# Sch1.net
KiCad netlist of a schematic drawn in EAGLE
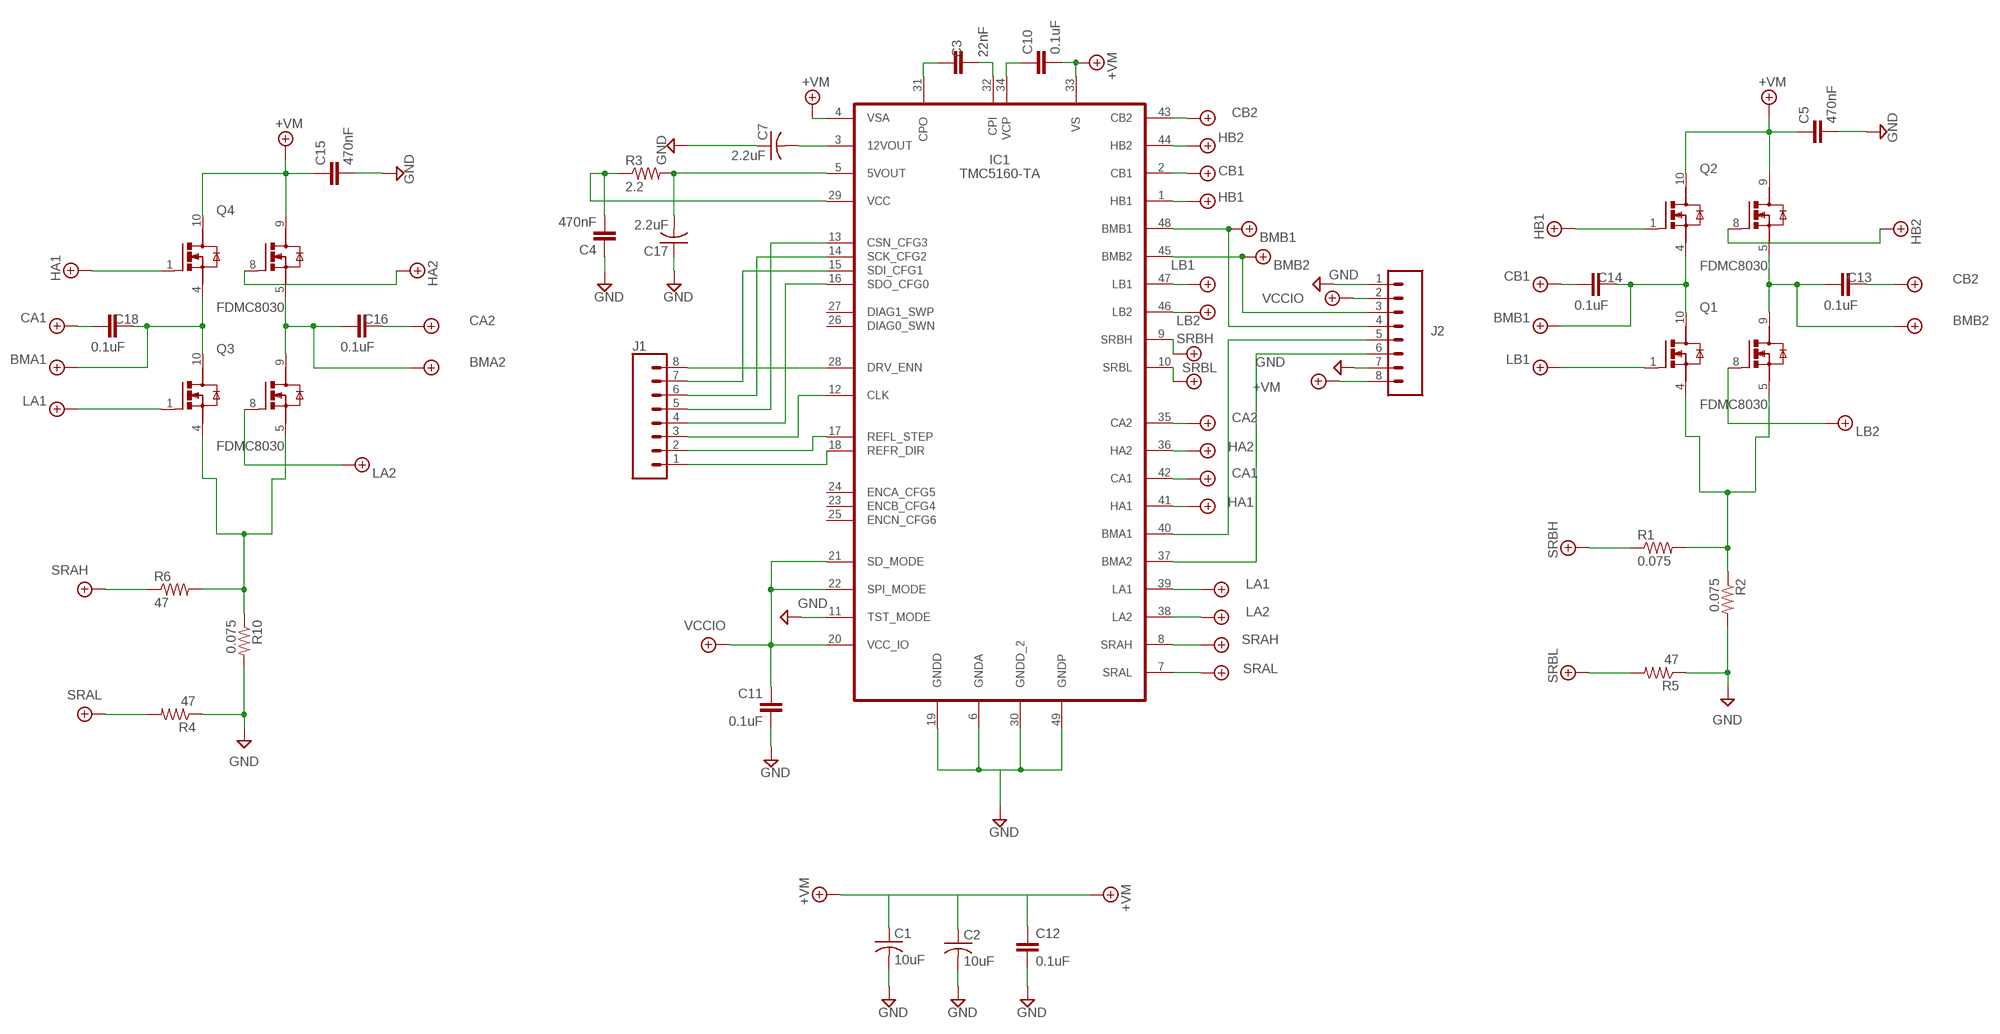
[diagram p0: schematic, sheet 1]

(export (version "E")
  (design (tool "Eeschema 10.0.6"))
  (components
    (comp (ref "C1")
      (value "10uF")
      (footprint "eagle-import:C0805")
      (libsource (lib "eagle-import") (part "C-USC0805"))
    )
    (comp (ref "C2")
      (value "10uF")
      (footprint "eagle-import:C0805")
      (libsource (lib "eagle-import") (part "C-USC0805"))
    )
    (comp (ref "C3")
      (value "22nF")
      (footprint "eagle-import:0603")
      (libsource (lib "eagle-import") (part "22NF/22,000PF-0603-50V-10%"))
    )
    (comp (ref "C4")
      (value "470nF")
      (footprint "eagle-import:0402")
      (libsource (lib "eagle-import") (part "470NF-0402-16V-10%"))
    )
    (comp (ref "C5")
      (value "470nF")
      (footprint "eagle-import:0402")
      (libsource (lib "eagle-import") (part "470NF-0402-16V-10%"))
    )
    (comp (ref "C7")
      (value "2.2uF")
      (footprint "eagle-import:C0402")
      (libsource (lib "eagle-import") (part "C-USC0402"))
    )
    (comp (ref "C10")
      (value "0.1uF")
      (footprint "eagle-import:0402")
      (libsource (lib "eagle-import") (part "0.1UF-0402-16V-10%"))
    )
    (comp (ref "C11")
      (value "0.1uF")
      (footprint "eagle-import:0402")
      (libsource (lib "eagle-import") (part "0.1UF-0402-16V-10%"))
    )
    (comp (ref "C12")
      (value "0.1uF")
      (footprint "eagle-import:0402")
      (libsource (lib "eagle-import") (part "0.1UF-0402-16V-10%"))
    )
    (comp (ref "C13")
      (value "0.1uF")
      (footprint "eagle-import:0402")
      (libsource (lib "eagle-import") (part "0.1UF-0402-16V-10%"))
    )
    (comp (ref "C14")
      (value "0.1uF")
      (footprint "eagle-import:0402")
      (libsource (lib "eagle-import") (part "0.1UF-0402-16V-10%"))
    )
    (comp (ref "C15")
      (value "470nF")
      (footprint "eagle-import:0402")
      (libsource (lib "eagle-import") (part "470NF-0402-16V-10%"))
    )
    (comp (ref "C16")
      (value "0.1uF")
      (footprint "eagle-import:0402")
      (libsource (lib "eagle-import") (part "0.1UF-0402-16V-10%"))
    )
    (comp (ref "C17")
      (value "2.2uF")
      (footprint "eagle-import:C0402")
      (libsource (lib "eagle-import") (part "C-USC0402"))
    )
    (comp (ref "C18")
      (value "0.1uF")
      (footprint "eagle-import:0402")
      (libsource (lib "eagle-import") (part "0.1UF-0402-16V-10%"))
    )
    (comp (ref "IC1")
      (value "TMC5160-TA")
      (footprint "eagle-import:TQFP48-EP")
      (fields (field (name "MF") "Trinamic Motion"))
      (libsource (lib "eagle-import") (part "TMC5160-TA"))
    )
    (comp (ref "J1")
      (value "CONN_08\"")
      (footprint "eagle-import:1X08")
      (libsource (lib "eagle-import") (part "CONN_08{dblquote}"))
    )
    (comp (ref "J2")
      (value "CONN_08\"")
      (footprint "eagle-import:1X08")
      (libsource (lib "eagle-import") (part "CONN_08{dblquote}"))
    )
    (comp (ref "Q1")
      (value "FDMC8030")
      (footprint "eagle-import:TRANS_FDMC8030")
      (fields (field (name "MF") "ON Semiconductor"))
      (libsource (lib "eagle-import") (part "FDMC8030"))
    )
    (comp (ref "Q2")
      (value "FDMC8030")
      (footprint "eagle-import:TRANS_FDMC8030")
      (fields (field (name "MF") "ON Semiconductor"))
      (libsource (lib "eagle-import") (part "FDMC8030"))
    )
    (comp (ref "Q3")
      (value "FDMC8030")
      (footprint "eagle-import:TRANS_FDMC8030")
      (fields (field (name "MF") "ON Semiconductor"))
      (libsource (lib "eagle-import") (part "FDMC8030"))
    )
    (comp (ref "Q4")
      (value "FDMC8030")
      (footprint "eagle-import:TRANS_FDMC8030")
      (fields (field (name "MF") "ON Semiconductor"))
      (libsource (lib "eagle-import") (part "FDMC8030"))
    )
    (comp (ref "R1")
      (value "0.075")
      (footprint "eagle-import:R1206")
      (libsource (lib "eagle-import") (part "R-US_R1206"))
    )
    (comp (ref "R2")
      (value "0.075")
      (footprint "eagle-import:R1206")
      (libsource (lib "eagle-import") (part "R-US_R1206"))
    )
    (comp (ref "R3")
      (value "2.2")
      (footprint "eagle-import:R0402")
      (libsource (lib "eagle-import") (part "R-US_R0402"))
    )
    (comp (ref "R4")
      (value "47")
      (footprint "eagle-import:R0402")
      (libsource (lib "eagle-import") (part "R-US_R0402"))
    )
    (comp (ref "R5")
      (value "47")
      (footprint "eagle-import:R0402")
      (libsource (lib "eagle-import") (part "R-US_R0402"))
    )
    (comp (ref "R6")
      (value "47")
      (footprint "eagle-import:R0402")
      (libsource (lib "eagle-import") (part "R-US_R0402"))
    )
    (comp (ref "R10")
      (value "0.075")
      (footprint "eagle-import:R1206")
      (libsource (lib "eagle-import") (part "R-US_R1206"))
    )
  )
  (nets
    (net (code "1") (name "+VM") (class "Default")
      (node (ref "C1") (pin "1") (pinfunction "1_1") (pintype "passive"))
      (node (ref "C10") (pin "2") (pinfunction "2_2") (pintype "passive"))
      (node (ref "C12") (pin "1") (pinfunction "1_1") (pintype "passive"))
      (node (ref "C13") (pin "1") (pinfunction "1_1") (pintype "passive"))
      (node (ref "C13") (pin "2") (pinfunction "2_2") (pintype "passive"))
      (node (ref "C14") (pin "1") (pinfunction "1_1") (pintype "passive"))
      (node (ref "C14") (pin "2") (pinfunction "2_2") (pintype "passive"))
      (node (ref "C15") (pin "1") (pinfunction "1_1") (pintype "passive"))
      (node (ref "C16") (pin "1") (pinfunction "1_1") (pintype "passive"))
      (node (ref "C16") (pin "2") (pinfunction "2_2") (pintype "passive"))
      (node (ref "C18") (pin "1") (pinfunction "1_1") (pintype "passive"))
      (node (ref "C18") (pin "2") (pinfunction "2_2") (pintype "passive"))
      (node (ref "C2") (pin "1") (pinfunction "1_1") (pintype "passive"))
      (node (ref "C5") (pin "1") (pinfunction "1_1") (pintype "passive"))
      (node (ref "IC1") (pin "1") (pinfunction "HB1_1") (pintype "output"))
      (node (ref "IC1") (pin "10") (pinfunction "SRBL_10") (pintype "input"))
      (node (ref "IC1") (pin "2") (pinfunction "CB1_2") (pintype "input"))
      (node (ref "IC1") (pin "33") (pinfunction "VS_33") (pintype "power_in"))
      (node (ref "IC1") (pin "35") (pinfunction "CA2_35") (pintype "input"))
      (node (ref "IC1") (pin "36") (pinfunction "HA2_36") (pintype "output"))
      (node (ref "IC1") (pin "38") (pinfunction "LA2_38") (pintype "output"))
      (node (ref "IC1") (pin "39") (pinfunction "LA1_39") (pintype "output"))
      (node (ref "IC1") (pin "4") (pinfunction "VSA_4") (pintype "power_in"))
      (node (ref "IC1") (pin "41") (pinfunction "HA1_41") (pintype "output"))
      (node (ref "IC1") (pin "42") (pinfunction "CA1_42") (pintype "input"))
      (node (ref "IC1") (pin "43") (pinfunction "CB2_43") (pintype "input"))
      (node (ref "IC1") (pin "44") (pinfunction "HB2_44") (pintype "output"))
      (node (ref "IC1") (pin "45") (pinfunction "BMB2_45") (pintype "input"))
      (node (ref "IC1") (pin "46") (pinfunction "LB2_46") (pintype "output"))
      (node (ref "IC1") (pin "47") (pinfunction "LB1_47") (pintype "output"))
      (node (ref "IC1") (pin "48") (pinfunction "BMB1_48") (pintype "input"))
      (node (ref "IC1") (pin "7") (pinfunction "SRAL_7") (pintype "input"))
      (node (ref "IC1") (pin "8") (pinfunction "SRAH_8") (pintype "input"))
      (node (ref "IC1") (pin "9") (pinfunction "SRBH_9") (pintype "input"))
      (node (ref "J2") (pin "3") (pinfunction "3_3") (pintype "passive"))
      (node (ref "J2") (pin "4") (pinfunction "4_4") (pintype "passive"))
      (node (ref "J2") (pin "8") (pinfunction "8_8") (pintype "passive"))
      (node (ref "Q1") (pin "1") (pinfunction "G1_1") (pintype "passive"))
      (node (ref "Q1") (pin "10") (pinfunction "D1_10") (pintype "passive"))
      (node (ref "Q1") (pin "8") (pinfunction "G2_8") (pintype "passive"))
      (node (ref "Q1") (pin "9") (pinfunction "D2_9") (pintype "passive"))
      (node (ref "Q2") (pin "1") (pinfunction "G1_1") (pintype "passive"))
      (node (ref "Q2") (pin "10") (pinfunction "D1_10") (pintype "passive"))
      (node (ref "Q2") (pin "4") (pinfunction "S1_4") (pintype "passive"))
      (node (ref "Q2") (pin "5") (pinfunction "S2_5") (pintype "passive"))
      (node (ref "Q2") (pin "8") (pinfunction "G2_8") (pintype "passive"))
      (node (ref "Q2") (pin "9") (pinfunction "D2_9") (pintype "passive"))
      (node (ref "Q3") (pin "1") (pinfunction "G1_1") (pintype "passive"))
      (node (ref "Q3") (pin "10") (pinfunction "D1_10") (pintype "passive"))
      (node (ref "Q3") (pin "8") (pinfunction "G2_8") (pintype "passive"))
      (node (ref "Q3") (pin "9") (pinfunction "D2_9") (pintype "passive"))
      (node (ref "Q4") (pin "1") (pinfunction "G1_1") (pintype "passive"))
      (node (ref "Q4") (pin "10") (pinfunction "D1_10") (pintype "passive"))
      (node (ref "Q4") (pin "4") (pinfunction "S1_4") (pintype "passive"))
      (node (ref "Q4") (pin "5") (pinfunction "S2_5") (pintype "passive"))
      (node (ref "Q4") (pin "8") (pinfunction "G2_8") (pintype "passive"))
      (node (ref "Q4") (pin "9") (pinfunction "D2_9") (pintype "passive"))
      (node (ref "R1") (pin "1") (pinfunction "1_1") (pintype "passive"))
      (node (ref "R4") (pin "2") (pinfunction "2_2") (pintype "passive"))
      (node (ref "R5") (pin "2") (pinfunction "2_2") (pintype "passive"))
      (node (ref "R6") (pin "1") (pinfunction "1_1") (pintype "passive"))
    )
    (net (code "2") (name "GND") (class "Default")
      (node (ref "C1") (pin "2") (pinfunction "2_2") (pintype "passive"))
      (node (ref "C11") (pin "2") (pinfunction "2_2") (pintype "passive"))
      (node (ref "C12") (pin "2") (pinfunction "2_2") (pintype "passive"))
      (node (ref "C15") (pin "2") (pinfunction "2_2") (pintype "passive"))
      (node (ref "C17") (pin "1") (pinfunction "1_1") (pintype "passive"))
      (node (ref "C2") (pin "2") (pinfunction "2_2") (pintype "passive"))
      (node (ref "C4") (pin "1") (pinfunction "1_1") (pintype "passive"))
      (node (ref "C5") (pin "2") (pinfunction "2_2") (pintype "passive"))
      (node (ref "C7") (pin "1") (pinfunction "1_1") (pintype "passive"))
      (node (ref "IC1") (pin "11") (pinfunction "TST_MODE_11") (pintype "input"))
      (node (ref "IC1") (pin "19") (pinfunction "GNDD_19") (pintype "power_in"))
      (node (ref "IC1") (pin "30") (pinfunction "GNDD_2_30") (pintype "power_in"))
      (node (ref "IC1") (pin "49") (pinfunction "GNDP_49") (pintype "power_in"))
      (node (ref "IC1") (pin "6") (pinfunction "GNDA_6") (pintype "power_in"))
      (node (ref "J2") (pin "1") (pinfunction "1_1") (pintype "passive"))
      (node (ref "J2") (pin "7") (pinfunction "7_7") (pintype "passive"))
      (node (ref "R10") (pin "2") (pinfunction "2_2") (pintype "passive"))
      (node (ref "R2") (pin "2") (pinfunction "2_2") (pintype "passive"))
      (node (ref "R4") (pin "1") (pinfunction "1_1") (pintype "passive"))
      (node (ref "R5") (pin "1") (pinfunction "1_1") (pintype "passive"))
    )
    (net (code "3") (name "Net-(IC1-5VOUT)") (class "Default")
      (node (ref "C17") (pin "2") (pinfunction "2_2") (pintype "passive"))
      (node (ref "IC1") (pin "5") (pinfunction "5VOUT_5") (pintype "bidirectional"))
      (node (ref "R3") (pin "2") (pinfunction "2_2") (pintype "passive"))
    )
    (net (code "4") (name "Net-(IC1-12VOUT)") (class "Default")
      (node (ref "C7") (pin "2") (pinfunction "2_2") (pintype "passive"))
      (node (ref "IC1") (pin "3") (pinfunction "12VOUT_3") (pintype "bidirectional"))
    )
    (net (code "5") (name "Net-(IC1-BMA1)") (class "Default")
      (node (ref "IC1") (pin "40") (pinfunction "BMA1_40") (pintype "input"))
      (node (ref "J2") (pin "5") (pinfunction "5_5") (pintype "passive"))
    )
    (net (code "6") (name "Net-(IC1-BMA2)") (class "Default")
      (node (ref "IC1") (pin "37") (pinfunction "BMA2_37") (pintype "input"))
      (node (ref "J2") (pin "6") (pinfunction "6_6") (pintype "passive"))
    )
    (net (code "7") (name "Net-(IC1-CLK)") (class "Default")
      (node (ref "IC1") (pin "12") (pinfunction "CLK_12") (pintype "input"))
      (node (ref "J1") (pin "3") (pinfunction "3_3") (pintype "passive"))
    )
    (net (code "8") (name "Net-(IC1-CPI)") (class "Default")
      (node (ref "C3") (pin "2") (pinfunction "2_2") (pintype "passive"))
      (node (ref "IC1") (pin "32") (pinfunction "CPI_32") (pintype "input"))
    )
    (net (code "9") (name "Net-(IC1-CPO)") (class "Default")
      (node (ref "C3") (pin "1") (pinfunction "1_1") (pintype "passive"))
      (node (ref "IC1") (pin "31") (pinfunction "CPO_31") (pintype "input"))
    )
    (net (code "10") (name "Net-(IC1-CSN_CFG3)") (class "Default")
      (node (ref "IC1") (pin "13") (pinfunction "CSN_CFG3_13") (pintype "input"))
      (node (ref "J1") (pin "5") (pinfunction "5_5") (pintype "passive"))
    )
    (net (code "11") (name "Net-(IC1-DRV_ENN)") (class "Default")
      (node (ref "IC1") (pin "28") (pinfunction "DRV_ENN_28") (pintype "input"))
      (node (ref "J1") (pin "8") (pinfunction "8_8") (pintype "passive"))
    )
    (net (code "12") (name "Net-(IC1-REFL_STEP)") (class "Default")
      (node (ref "IC1") (pin "17") (pinfunction "REFL_STEP_17") (pintype "input"))
      (node (ref "J1") (pin "2") (pinfunction "2_2") (pintype "passive"))
    )
    (net (code "13") (name "Net-(IC1-REFR_DIR)") (class "Default")
      (node (ref "IC1") (pin "18") (pinfunction "REFR_DIR_18") (pintype "input"))
      (node (ref "J1") (pin "1") (pinfunction "1_1") (pintype "passive"))
    )
    (net (code "14") (name "Net-(IC1-SCK_CFG2)") (class "Default")
      (node (ref "IC1") (pin "14") (pinfunction "SCK_CFG2_14") (pintype "input"))
      (node (ref "J1") (pin "6") (pinfunction "6_6") (pintype "passive"))
    )
    (net (code "15") (name "Net-(IC1-SDI_CFG1)") (class "Default")
      (node (ref "IC1") (pin "15") (pinfunction "SDI_CFG1_15") (pintype "input"))
      (node (ref "J1") (pin "7") (pinfunction "7_7") (pintype "passive"))
    )
    (net (code "16") (name "Net-(IC1-SDO_CFG0)") (class "Default")
      (node (ref "IC1") (pin "16") (pinfunction "SDO_CFG0_16") (pintype "output"))
      (node (ref "J1") (pin "4") (pinfunction "4_4") (pintype "passive"))
    )
    (net (code "17") (name "Net-(IC1-VCC)") (class "Default")
      (node (ref "C4") (pin "2") (pinfunction "2_2") (pintype "passive"))
      (node (ref "IC1") (pin "29") (pinfunction "VCC_29") (pintype "power_in"))
      (node (ref "R3") (pin "1") (pinfunction "1_1") (pintype "passive"))
    )
    (net (code "18") (name "Net-(IC1-VCP)") (class "Default")
      (node (ref "C10") (pin "1") (pinfunction "1_1") (pintype "passive"))
      (node (ref "IC1") (pin "34") (pinfunction "VCP_34") (pintype "input"))
    )
    (net (code "19") (name "Net-(Q1-S1)") (class "Default")
      (node (ref "Q1") (pin "4") (pinfunction "S1_4") (pintype "passive"))
      (node (ref "Q1") (pin "5") (pinfunction "S2_5") (pintype "passive"))
      (node (ref "R1") (pin "2") (pinfunction "2_2") (pintype "passive"))
      (node (ref "R2") (pin "1") (pinfunction "1_1") (pintype "passive"))
    )
    (net (code "20") (name "Net-(Q3-S1)") (class "Default")
      (node (ref "Q3") (pin "4") (pinfunction "S1_4") (pintype "passive"))
      (node (ref "Q3") (pin "5") (pinfunction "S2_5") (pintype "passive"))
      (node (ref "R10") (pin "1") (pinfunction "1_1") (pintype "passive"))
      (node (ref "R6") (pin "2") (pinfunction "2_2") (pintype "passive"))
    )
    (net (code "21") (name "VCCIO") (class "Default")
      (node (ref "C11") (pin "1") (pinfunction "1_1") (pintype "passive"))
      (node (ref "IC1") (pin "20") (pinfunction "VCC_IO_20") (pintype "power_in"))
      (node (ref "IC1") (pin "21") (pinfunction "SD_MODE_21") (pintype "input"))
      (node (ref "IC1") (pin "22") (pinfunction "SPI_MODE_22") (pintype "input"))
      (node (ref "J2") (pin "2") (pinfunction "2_2") (pintype "passive"))
    )
    (net (code "22") (name "unconnected-(IC1-DIAG0_SWN-Pad26)") (class "Default")
      (node (ref "IC1") (pin "26") (pinfunction "DIAG0_SWN_26") (pintype "bidirectional"))
    )
    (net (code "23") (name "unconnected-(IC1-DIAG1_SWP-Pad27)") (class "Default")
      (node (ref "IC1") (pin "27") (pinfunction "DIAG1_SWP_27") (pintype "bidirectional"))
    )
    (net (code "24") (name "unconnected-(IC1-ENCA_CFG5-Pad24)") (class "Default")
      (node (ref "IC1") (pin "24") (pinfunction "ENCA_CFG5_24") (pintype "input"))
    )
    (net (code "25") (name "unconnected-(IC1-ENCB_CFG4-Pad23)") (class "Default")
      (node (ref "IC1") (pin "23") (pinfunction "ENCB_CFG4_23") (pintype "input"))
    )
    (net (code "26") (name "unconnected-(IC1-ENCN_CFG6-Pad25)") (class "Default")
      (node (ref "IC1") (pin "25") (pinfunction "ENCN_CFG6_25") (pintype "input"))
    )
  )
)
